# interface1.net
KiCad netlist of a schematic drawn in Altium Designer
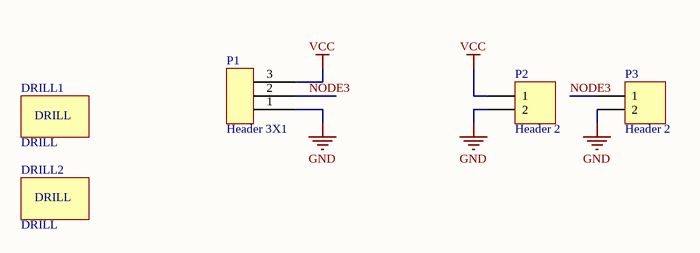
[diagram p0: interface1.SchDoc]

(export (version "E")
  (design (tool "Eeschema 10.0.6"))
  (components
    (comp (ref "DRILL1") (value "DRILL") (footprint "DRILL_2MM") (libsource (lib "Inte") (part "DRILL")))
    (comp (ref "DRILL2") (value "DRILL") (footprint "DRILL_2MM") (libsource (lib "Inte") (part "DRILL")))
    (comp (ref "P1")
      (value "Header 3X1")
      (footprint "HDR3X1")
      (description "Header 3X1,3-Pin")
      (libsource (lib "Inte") (part "Header 3X1"))
    )
    (comp (ref "P2")
      (value "Header 2")
      (footprint "HDR1X2")
      (description "Header, 2-Pin")
      (fields (field (name "PUBLISHER") "Altium Limited"))
      (libsource (lib "Miscellaneous Connectors") (part "Header 2"))
    )
    (comp (ref "P3")
      (value "Header 2")
      (footprint "HDR1X2")
      (description "Header, 2-Pin")
      (fields (field (name "PUBLISHER") "Altium Limited"))
      (libsource (lib "Miscellaneous Connectors") (part "Header 2"))
    )
  )
  (nets
    (net (code "1") (name "/NODE3") (class "Default")
      (node (ref "P1") (pin "2") (pinfunction "2_2") (pintype "passive"))
      (node (ref "P3") (pin "1") (pinfunction "1_1") (pintype "passive"))
    )
    (net (code "2") (name "GND") (class "Default")
      (node (ref "P1") (pin "1") (pinfunction "1_1") (pintype "passive"))
      (node (ref "P2") (pin "2") (pinfunction "2_2") (pintype "passive"))
      (node (ref "P3") (pin "2") (pinfunction "2_2") (pintype "passive"))
    )
    (net (code "3") (name "VCC") (class "Default")
      (node (ref "P1") (pin "3") (pinfunction "3_3") (pintype "passive"))
      (node (ref "P2") (pin "1") (pinfunction "1_1") (pintype "passive"))
    )
  )
)
